# 3DAM.net
KiCad netlist of a schematic drawn in EAGLE
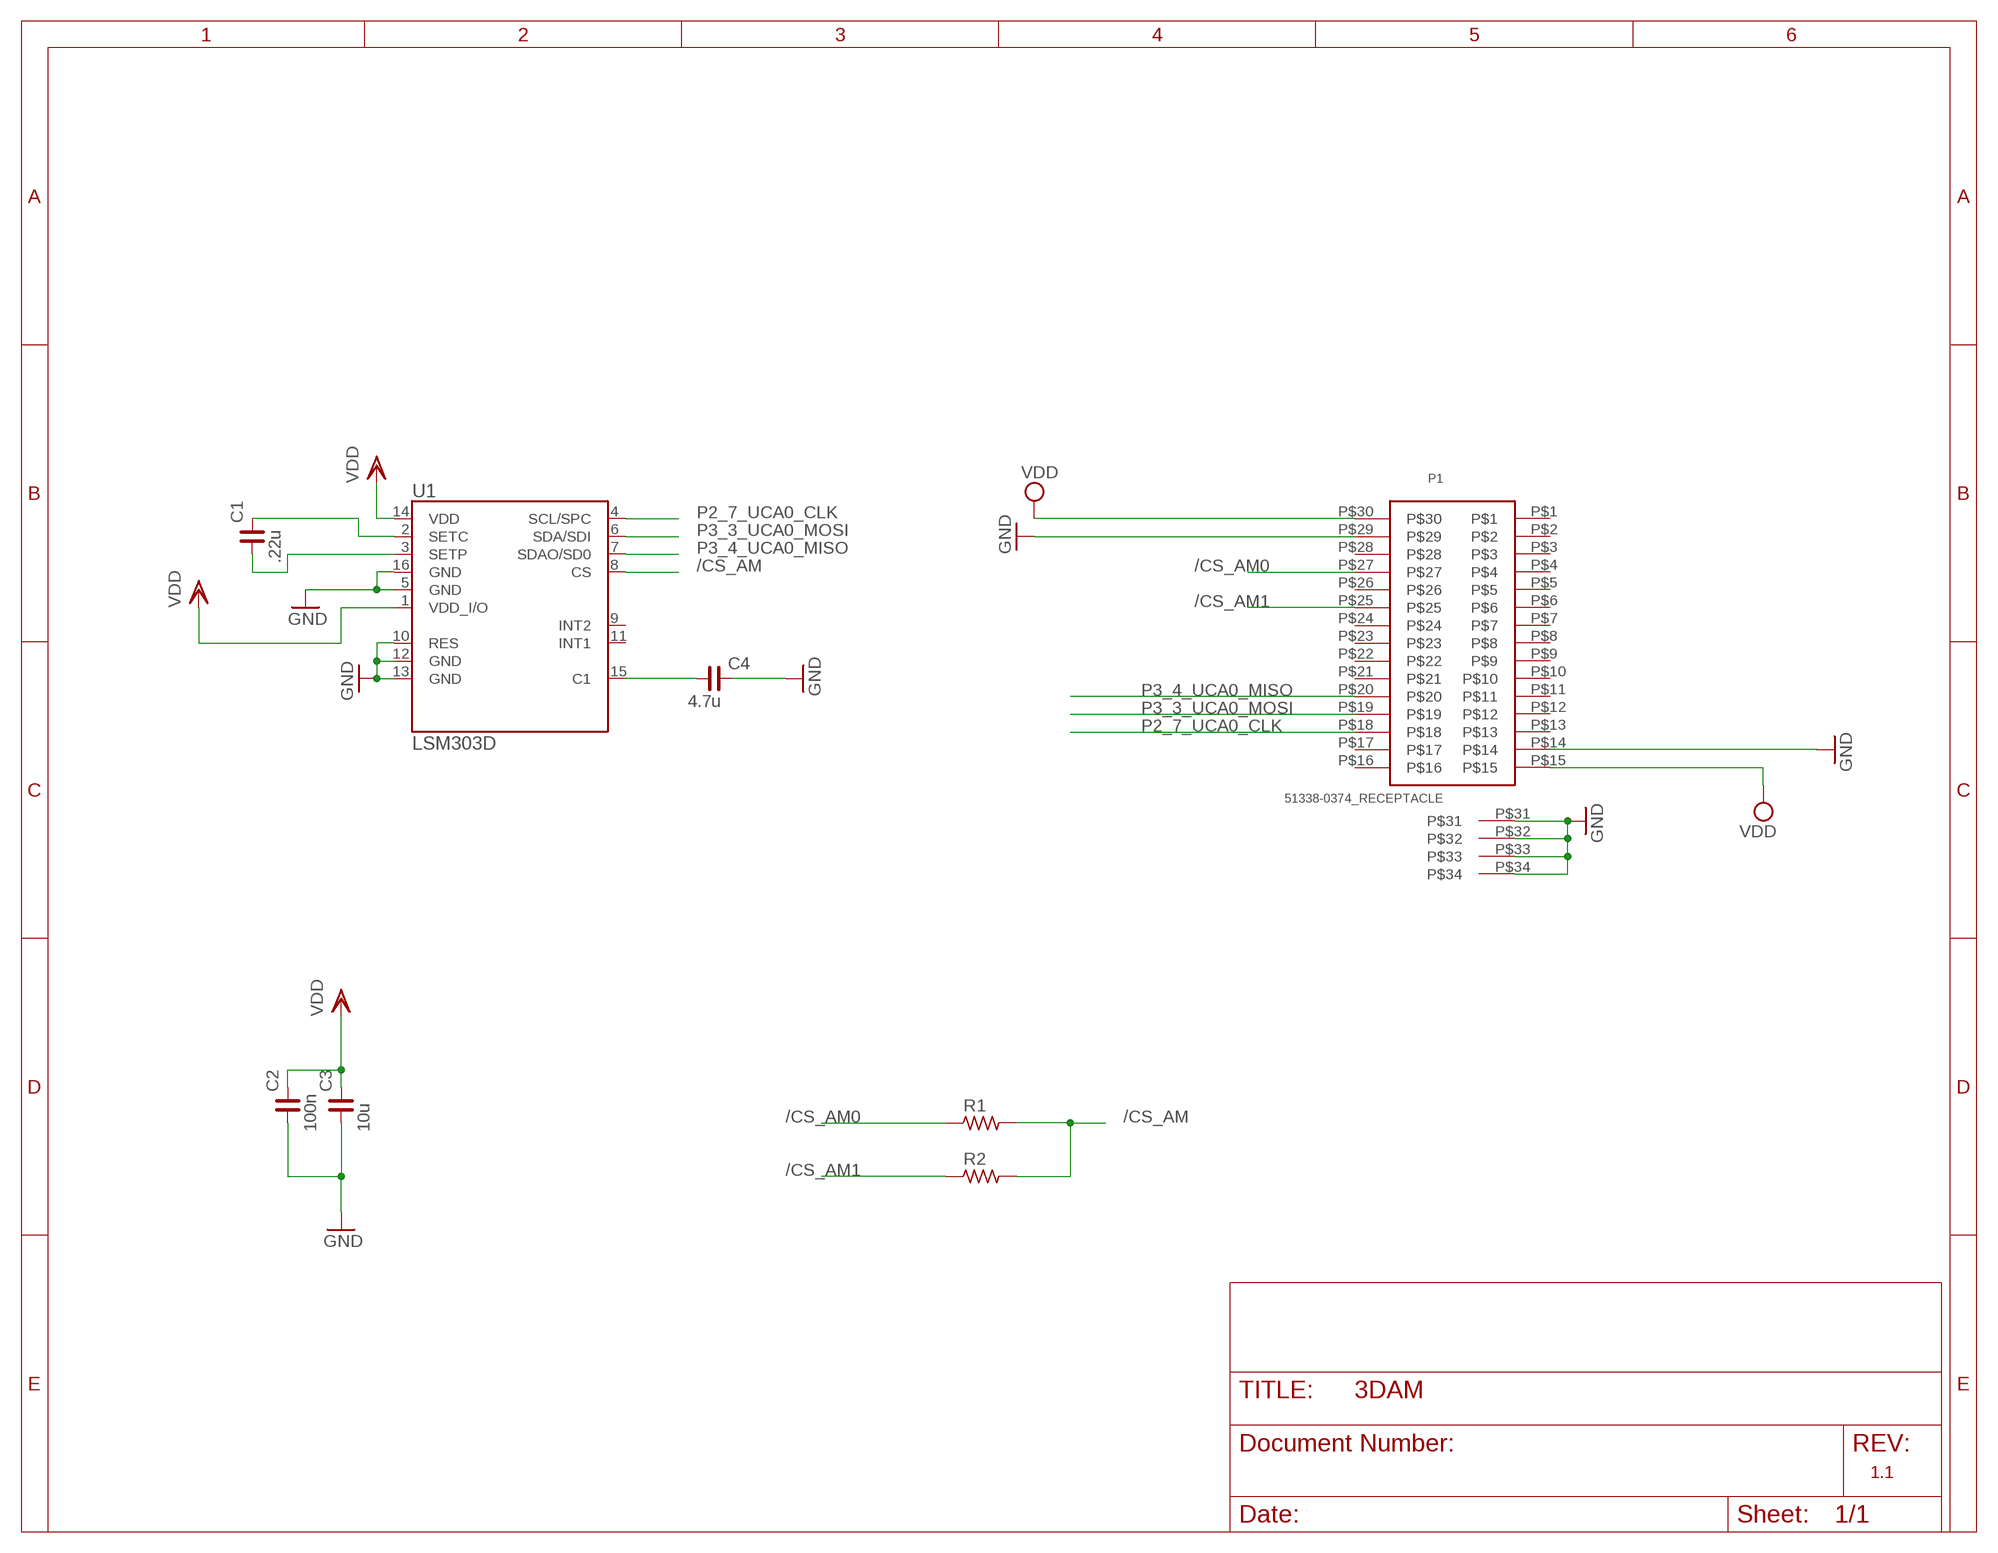
[diagram p0: schematic, sheet 1]

(export (version "E")
  (design (tool "Eeschema 10.0.6"))
  (components
    (comp (ref "C1")
      (value ".22u")
      (footprint "eagle-import:C0402")
      (libsource (lib "eagle-import") (part "C_0402"))
    )
    (comp (ref "C2")
      (value "100n")
      (footprint "eagle-import:C0402")
      (libsource (lib "eagle-import") (part "C_0402"))
    )
    (comp (ref "C3")
      (value "10u")
      (footprint "eagle-import:C0402")
      (libsource (lib "eagle-import") (part "C_0402"))
    )
    (comp (ref "C4")
      (value "4.7u")
      (footprint "eagle-import:C0402")
      (libsource (lib "eagle-import") (part "C_0402"))
    )
    (comp (ref "P1")
      (value "51338-0374_RECEPTACLE")
      (footprint "eagle-import:51338-0374_RECEPTACLE")
      (libsource (lib "eagle-import") (part "51338-0374_RECEPTACLE"))
    )
    (comp (ref "R1")
      (value "R_0402")
      (footprint "eagle-import:R0402")
      (libsource (lib "eagle-import") (part "R_0402"))
    )
    (comp (ref "R2")
      (value "R_0402")
      (footprint "eagle-import:R0402")
      (libsource (lib "eagle-import") (part "R_0402"))
    )
    (comp (ref "U1")
      (value "LSM303D")
      (footprint "eagle-import:LGA16-3MM")
      (libsource (lib "eagle-import") (part "LSM303D"))
    )
  )
  (nets
    (net (code "1") (name "/P2_7_UCA0_CLK") (class "Default")
      (node (ref "P1") (pin "P$18") (pinfunction "P$18_P$18") (pintype "bidirectional"))
      (node (ref "U1") (pin "4") (pinfunction "SCL/SPC_4") (pintype "bidirectional"))
    )
    (net (code "2") (name "/P3_3_UCA0_MOSI") (class "Default")
      (node (ref "P1") (pin "P$19") (pinfunction "P$19_P$19") (pintype "bidirectional"))
      (node (ref "U1") (pin "6") (pinfunction "SDA/SDI_6") (pintype "bidirectional"))
    )
    (net (code "3") (name "/P3_4_UCA0_MISO") (class "Default")
      (node (ref "P1") (pin "P$20") (pinfunction "P$20_P$20") (pintype "bidirectional"))
      (node (ref "U1") (pin "7") (pinfunction "SDAO/SD0_7") (pintype "bidirectional"))
    )
    (net (code "4") (name "/{slash}CS_AM") (class "Default")
      (node (ref "R1") (pin "2") (pinfunction "2_2") (pintype "passive"))
      (node (ref "R2") (pin "2") (pinfunction "2_2") (pintype "passive"))
      (node (ref "U1") (pin "8") (pinfunction "CS_8") (pintype "bidirectional"))
    )
    (net (code "5") (name "/{slash}CS_AM0") (class "Default")
      (node (ref "P1") (pin "P$27") (pinfunction "P$27_P$27") (pintype "bidirectional"))
      (node (ref "R1") (pin "1") (pinfunction "1_1") (pintype "passive"))
    )
    (net (code "6") (name "/{slash}CS_AM1") (class "Default")
      (node (ref "P1") (pin "P$25") (pinfunction "P$25_P$25") (pintype "bidirectional"))
      (node (ref "R2") (pin "1") (pinfunction "1_1") (pintype "passive"))
    )
    (net (code "7") (name "GND") (class "Default")
      (node (ref "C2") (pin "1") (pinfunction "1_1") (pintype "passive"))
      (node (ref "C3") (pin "1") (pinfunction "1_1") (pintype "passive"))
      (node (ref "C4") (pin "2") (pinfunction "2_2") (pintype "passive"))
      (node (ref "P1") (pin "P$14") (pinfunction "P$14_P$14") (pintype "bidirectional"))
      (node (ref "P1") (pin "P$29") (pinfunction "P$29_P$29") (pintype "bidirectional"))
      (node (ref "P1") (pin "P$31") (pinfunction "P$31_P$31") (pintype "bidirectional"))
      (node (ref "P1") (pin "P$32") (pinfunction "P$32_P$32") (pintype "bidirectional"))
      (node (ref "P1") (pin "P$33") (pinfunction "P$33_P$33") (pintype "bidirectional"))
      (node (ref "P1") (pin "P$34") (pinfunction "P$34_P$34") (pintype "bidirectional"))
      (node (ref "U1") (pin "10") (pinfunction "RES_10") (pintype "bidirectional"))
      (node (ref "U1") (pin "12") (pinfunction "GND_12") (pintype "bidirectional"))
      (node (ref "U1") (pin "13") (pinfunction "GND_13") (pintype "bidirectional"))
      (node (ref "U1") (pin "16") (pinfunction "GND_16") (pintype "bidirectional"))
      (node (ref "U1") (pin "5") (pinfunction "GND_5") (pintype "bidirectional"))
    )
    (net (code "8") (name "Net-(U1-C1)") (class "Default")
      (node (ref "C4") (pin "1") (pinfunction "1_1") (pintype "passive"))
      (node (ref "U1") (pin "15") (pinfunction "C1_15") (pintype "bidirectional"))
    )
    (net (code "9") (name "Net-(U1-SETC)") (class "Default")
      (node (ref "C1") (pin "2") (pinfunction "2_2") (pintype "passive"))
      (node (ref "U1") (pin "2") (pinfunction "SETC_2") (pintype "bidirectional"))
    )
    (net (code "10") (name "Net-(U1-SETP)") (class "Default")
      (node (ref "C1") (pin "1") (pinfunction "1_1") (pintype "passive"))
      (node (ref "U1") (pin "3") (pinfunction "SETP_3") (pintype "bidirectional"))
    )
    (net (code "11") (name "VDD") (class "Default")
      (node (ref "C2") (pin "2") (pinfunction "2_2") (pintype "passive"))
      (node (ref "C3") (pin "2") (pinfunction "2_2") (pintype "passive"))
      (node (ref "P1") (pin "P$15") (pinfunction "P$15_P$15") (pintype "bidirectional"))
      (node (ref "P1") (pin "P$30") (pinfunction "P$30_P$30") (pintype "bidirectional"))
      (node (ref "U1") (pin "1") (pinfunction "VDD_I/O_1") (pintype "bidirectional"))
      (node (ref "U1") (pin "14") (pinfunction "VDD_14") (pintype "bidirectional"))
    )
    (net (code "12") (name "unconnected-(P1-PadP$1)") (class "Default")
      (node (ref "P1") (pin "P$1") (pinfunction "P$1_P$1") (pintype "bidirectional"))
    )
    (net (code "13") (name "unconnected-(P1-PadP$2)") (class "Default")
      (node (ref "P1") (pin "P$2") (pinfunction "P$2_P$2") (pintype "bidirectional"))
    )
    (net (code "14") (name "unconnected-(P1-PadP$3)") (class "Default")
      (node (ref "P1") (pin "P$3") (pinfunction "P$3_P$3") (pintype "bidirectional"))
    )
    (net (code "15") (name "unconnected-(P1-PadP$4)") (class "Default")
      (node (ref "P1") (pin "P$4") (pinfunction "P$4_P$4") (pintype "bidirectional"))
    )
    (net (code "16") (name "unconnected-(P1-PadP$5)") (class "Default")
      (node (ref "P1") (pin "P$5") (pinfunction "P$5_P$5") (pintype "bidirectional"))
    )
    (net (code "17") (name "unconnected-(P1-PadP$6)") (class "Default")
      (node (ref "P1") (pin "P$6") (pinfunction "P$6_P$6") (pintype "bidirectional"))
    )
    (net (code "18") (name "unconnected-(P1-PadP$7)") (class "Default")
      (node (ref "P1") (pin "P$7") (pinfunction "P$7_P$7") (pintype "bidirectional"))
    )
    (net (code "19") (name "unconnected-(P1-PadP$8)") (class "Default")
      (node (ref "P1") (pin "P$8") (pinfunction "P$8_P$8") (pintype "bidirectional"))
    )
    (net (code "20") (name "unconnected-(P1-PadP$9)") (class "Default")
      (node (ref "P1") (pin "P$9") (pinfunction "P$9_P$9") (pintype "bidirectional"))
    )
    (net (code "21") (name "unconnected-(P1-PadP$10)") (class "Default")
      (node (ref "P1") (pin "P$10") (pinfunction "P$10_P$10") (pintype "bidirectional"))
    )
    (net (code "22") (name "unconnected-(P1-PadP$11)") (class "Default")
      (node (ref "P1") (pin "P$11") (pinfunction "P$11_P$11") (pintype "bidirectional"))
    )
    (net (code "23") (name "unconnected-(P1-PadP$12)") (class "Default")
      (node (ref "P1") (pin "P$12") (pinfunction "P$12_P$12") (pintype "bidirectional"))
    )
    (net (code "24") (name "unconnected-(P1-PadP$13)") (class "Default")
      (node (ref "P1") (pin "P$13") (pinfunction "P$13_P$13") (pintype "bidirectional"))
    )
    (net (code "25") (name "unconnected-(P1-PadP$16)") (class "Default")
      (node (ref "P1") (pin "P$16") (pinfunction "P$16_P$16") (pintype "bidirectional"))
    )
    (net (code "26") (name "unconnected-(P1-PadP$17)") (class "Default")
      (node (ref "P1") (pin "P$17") (pinfunction "P$17_P$17") (pintype "bidirectional"))
    )
    (net (code "27") (name "unconnected-(P1-PadP$21)") (class "Default")
      (node (ref "P1") (pin "P$21") (pinfunction "P$21_P$21") (pintype "bidirectional"))
    )
    (net (code "28") (name "unconnected-(P1-PadP$22)") (class "Default")
      (node (ref "P1") (pin "P$22") (pinfunction "P$22_P$22") (pintype "bidirectional"))
    )
    (net (code "29") (name "unconnected-(P1-PadP$23)") (class "Default")
      (node (ref "P1") (pin "P$23") (pinfunction "P$23_P$23") (pintype "bidirectional"))
    )
    (net (code "30") (name "unconnected-(P1-PadP$24)") (class "Default")
      (node (ref "P1") (pin "P$24") (pinfunction "P$24_P$24") (pintype "bidirectional"))
    )
    (net (code "31") (name "unconnected-(P1-PadP$26)") (class "Default")
      (node (ref "P1") (pin "P$26") (pinfunction "P$26_P$26") (pintype "bidirectional"))
    )
    (net (code "32") (name "unconnected-(P1-PadP$28)") (class "Default")
      (node (ref "P1") (pin "P$28") (pinfunction "P$28_P$28") (pintype "bidirectional"))
    )
    (net (code "33") (name "unconnected-(U1-INT1-Pad11)") (class "Default")
      (node (ref "U1") (pin "11") (pinfunction "INT1_11") (pintype "bidirectional"))
    )
    (net (code "34") (name "unconnected-(U1-INT2-Pad9)") (class "Default")
      (node (ref "U1") (pin "9") (pinfunction "INT2_9") (pintype "bidirectional"))
    )
  )
)
